# phase-90.net
KiCad netlist of a schematic drawn in EAGLE
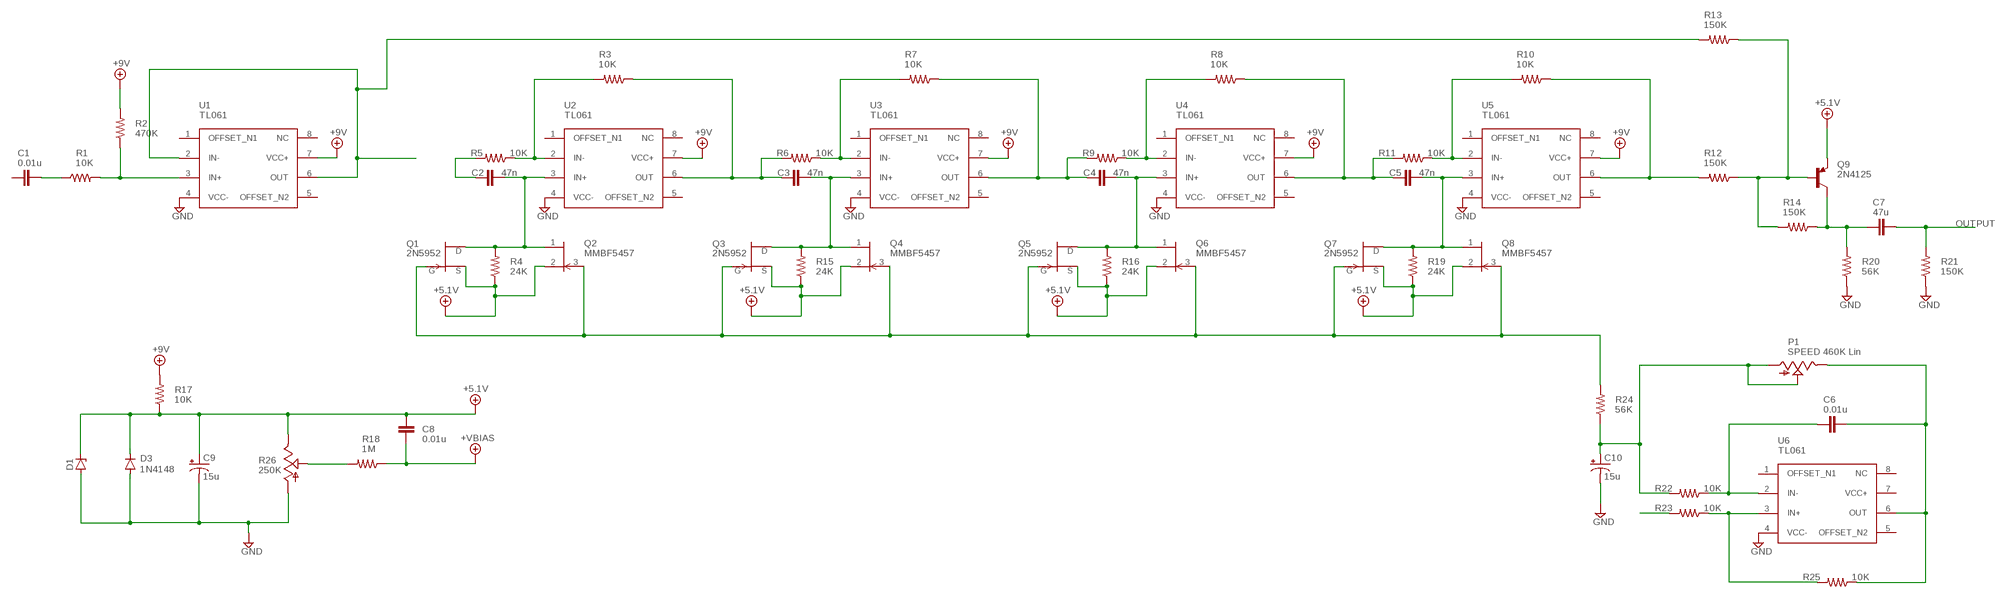
[diagram p0: schematic, sheet 1]

(export (version "E")
  (design (tool "Eeschema 10.0.6"))
  (components
    (comp (ref "C1")
      (value "0.01u")
      (footprint "eagle-import:C050-024X044")
      (libsource (lib "eagle-import") (part "C-EU050-024X044"))
    )
    (comp (ref "C2")
      (value "47n")
      (footprint "eagle-import:C050-024X044")
      (libsource (lib "eagle-import") (part "C-EU050-024X044"))
    )
    (comp (ref "C3")
      (value "47n")
      (footprint "eagle-import:C050-024X044")
      (libsource (lib "eagle-import") (part "C-EU050-024X044"))
    )
    (comp (ref "C4")
      (value "47n")
      (footprint "eagle-import:C050-024X044")
      (libsource (lib "eagle-import") (part "C-EU050-024X044"))
    )
    (comp (ref "C5")
      (value "47n")
      (footprint "eagle-import:C050-024X044")
      (libsource (lib "eagle-import") (part "C-EU050-024X044"))
    )
    (comp (ref "C6")
      (value "0.01u")
      (footprint "eagle-import:C050-024X044")
      (libsource (lib "eagle-import") (part "C-EU050-024X044"))
    )
    (comp (ref "C7")
      (value "47u")
      (footprint "eagle-import:C050-024X044")
      (libsource (lib "eagle-import") (part "C-EU050-024X044"))
    )
    (comp (ref "C8")
      (value "0.01u")
      (footprint "eagle-import:C050-024X044")
      (libsource (lib "eagle-import") (part "C-EU050-024X044"))
    )
    (comp (ref "C9")
      (value "15u")
      (footprint "eagle-import:E3,5-8")
      (libsource (lib "eagle-import") (part "CPOL-USE3.5-8"))
    )
    (comp (ref "C10")
      (value "15u")
      (footprint "eagle-import:E3,5-8")
      (libsource (lib "eagle-import") (part "CPOL-USE3.5-8"))
    )
    (comp (ref "D1")
      (value "ZENER-DIODEDO34-7")
      (footprint "eagle-import:DO34Z7")
      (libsource (lib "eagle-import") (part "ZENER-DIODEDO34-7"))
    )
    (comp (ref "D3")
      (value "1N4148")
      (footprint "eagle-import:DO35-7")
      (libsource (lib "eagle-import") (part "1N4148DO35-7"))
    )
    (comp (ref "P1")
      (value "SPEED 460K Lin")
      (footprint "eagle-import:POT-5.08MM")
      (libsource (lib "eagle-import") (part "POT"))
    )
    (comp (ref "Q1")
      (value "2N5952")
      (footprint "eagle-import:TO-92")
      (libsource (lib "eagle-import") (part "2N5950"))
    )
    (comp (ref "Q2")
      (value "MMBF5457")
      (footprint "eagle-import:SOT23")
      (libsource (lib "eagle-import") (part "MMBF5457"))
    )
    (comp (ref "Q3")
      (value "2N5952")
      (footprint "eagle-import:TO-92")
      (libsource (lib "eagle-import") (part "2N5950"))
    )
    (comp (ref "Q4")
      (value "MMBF5457")
      (footprint "eagle-import:SOT23")
      (libsource (lib "eagle-import") (part "MMBF5457"))
    )
    (comp (ref "Q5")
      (value "2N5952")
      (footprint "eagle-import:TO-92")
      (libsource (lib "eagle-import") (part "2N5950"))
    )
    (comp (ref "Q6")
      (value "MMBF5457")
      (footprint "eagle-import:SOT23")
      (libsource (lib "eagle-import") (part "MMBF5457"))
    )
    (comp (ref "Q7")
      (value "2N5952")
      (footprint "eagle-import:TO-92")
      (libsource (lib "eagle-import") (part "2N5950"))
    )
    (comp (ref "Q8")
      (value "MMBF5457")
      (footprint "eagle-import:SOT23")
      (libsource (lib "eagle-import") (part "MMBF5457"))
    )
    (comp (ref "Q9")
      (value "2N4125")
      (footprint "eagle-import:TO92")
      (libsource (lib "eagle-import") (part "-PNP-TO92"))
    )
    (comp (ref "R1")
      (value "10K")
      (footprint "eagle-import:0309_12")
      (libsource (lib "eagle-import") (part "R-US_0309/12"))
    )
    (comp (ref "R2")
      (value "470K")
      (footprint "eagle-import:0309_12")
      (libsource (lib "eagle-import") (part "R-US_0309/12"))
    )
    (comp (ref "R3")
      (value "10K")
      (footprint "eagle-import:0309_12")
      (libsource (lib "eagle-import") (part "R-US_0309/12"))
    )
    (comp (ref "R4")
      (value "24K")
      (footprint "eagle-import:0309_12")
      (libsource (lib "eagle-import") (part "R-US_0309/12"))
    )
    (comp (ref "R5")
      (value "10K")
      (footprint "eagle-import:0309_12")
      (libsource (lib "eagle-import") (part "R-US_0309/12"))
    )
    (comp (ref "R6")
      (value "10K")
      (footprint "eagle-import:0309_12")
      (libsource (lib "eagle-import") (part "R-US_0309/12"))
    )
    (comp (ref "R7")
      (value "10K")
      (footprint "eagle-import:0309_12")
      (libsource (lib "eagle-import") (part "R-US_0309/12"))
    )
    (comp (ref "R8")
      (value "10K")
      (footprint "eagle-import:0309_12")
      (libsource (lib "eagle-import") (part "R-US_0309/12"))
    )
    (comp (ref "R9")
      (value "10K")
      (footprint "eagle-import:0309_12")
      (libsource (lib "eagle-import") (part "R-US_0309/12"))
    )
    (comp (ref "R10")
      (value "10K")
      (footprint "eagle-import:0309_12")
      (libsource (lib "eagle-import") (part "R-US_0309/12"))
    )
    (comp (ref "R11")
      (value "10K")
      (footprint "eagle-import:0309_12")
      (libsource (lib "eagle-import") (part "R-US_0309/12"))
    )
    (comp (ref "R12")
      (value "150K")
      (footprint "eagle-import:0309_12")
      (libsource (lib "eagle-import") (part "R-US_0309/12"))
    )
    (comp (ref "R13")
      (value "150K")
      (footprint "eagle-import:0309_12")
      (libsource (lib "eagle-import") (part "R-US_0309/12"))
    )
    (comp (ref "R14")
      (value "150K")
      (footprint "eagle-import:0309_12")
      (libsource (lib "eagle-import") (part "R-US_0309/12"))
    )
    (comp (ref "R15")
      (value "24K")
      (footprint "eagle-import:0309_12")
      (libsource (lib "eagle-import") (part "R-US_0309/12"))
    )
    (comp (ref "R16")
      (value "24K")
      (footprint "eagle-import:0309_12")
      (libsource (lib "eagle-import") (part "R-US_0309/12"))
    )
    (comp (ref "R17")
      (value "10K")
      (footprint "eagle-import:0309_12")
      (libsource (lib "eagle-import") (part "R-US_0309/12"))
    )
    (comp (ref "R18")
      (value "1M")
      (footprint "eagle-import:0309_12")
      (libsource (lib "eagle-import") (part "R-US_0309/12"))
    )
    (comp (ref "R19")
      (value "24K")
      (footprint "eagle-import:0309_12")
      (libsource (lib "eagle-import") (part "R-US_0309/12"))
    )
    (comp (ref "R20")
      (value "56K")
      (footprint "eagle-import:0309_12")
      (libsource (lib "eagle-import") (part "R-US_0309/12"))
    )
    (comp (ref "R21")
      (value "150K")
      (footprint "eagle-import:0309_12")
      (libsource (lib "eagle-import") (part "R-US_0309/12"))
    )
    (comp (ref "R22")
      (value "10K")
      (footprint "eagle-import:0309_12")
      (libsource (lib "eagle-import") (part "R-US_0309/12"))
    )
    (comp (ref "R23")
      (value "10K")
      (footprint "eagle-import:0309_12")
      (libsource (lib "eagle-import") (part "R-US_0309/12"))
    )
    (comp (ref "R24")
      (value "56K")
      (footprint "eagle-import:0309_12")
      (libsource (lib "eagle-import") (part "R-US_0309/12"))
    )
    (comp (ref "R25")
      (value "10K")
      (footprint "eagle-import:0309_12")
      (libsource (lib "eagle-import") (part "R-US_0309/12"))
    )
    (comp (ref "R26")
      (value "250K")
      (footprint "eagle-import:CA6V")
      (libsource (lib "eagle-import") (part "TRIM_US-CA6V"))
    )
    (comp (ref "U1")
      (value "TL061")
      (footprint "eagle-import:DIL08")
      (libsource (lib "eagle-import") (part "TL061"))
    )
    (comp (ref "U2")
      (value "TL061")
      (footprint "eagle-import:DIL08")
      (libsource (lib "eagle-import") (part "TL061"))
    )
    (comp (ref "U3")
      (value "TL061")
      (footprint "eagle-import:DIL08")
      (libsource (lib "eagle-import") (part "TL061"))
    )
    (comp (ref "U4")
      (value "TL061")
      (footprint "eagle-import:DIL08")
      (libsource (lib "eagle-import") (part "TL061"))
    )
    (comp (ref "U5")
      (value "TL061")
      (footprint "eagle-import:DIL08")
      (libsource (lib "eagle-import") (part "TL061"))
    )
    (comp (ref "U6")
      (value "TL061")
      (footprint "eagle-import:DIL08")
      (libsource (lib "eagle-import") (part "TL061"))
    )
  )
  (nets
    (net (code "1") (name "+5.1V") (class "Default")
      (node (ref "C8") (pin "2") (pinfunction "2_2") (pintype "passive"))
      (node (ref "C9") (pin "+") (pinfunction "+_+") (pintype "passive"))
      (node (ref "D1") (pin "C") (pinfunction "C_C") (pintype "passive"))
      (node (ref "D3") (pin "C") (pinfunction "C_C") (pintype "passive"))
      (node (ref "Q1") (pin "2") (pinfunction "S_2") (pintype "passive"))
      (node (ref "Q2") (pin "2") (pinfunction "S_2") (pintype "passive"))
      (node (ref "Q3") (pin "2") (pinfunction "S_2") (pintype "passive"))
      (node (ref "Q4") (pin "2") (pinfunction "S_2") (pintype "passive"))
      (node (ref "Q5") (pin "2") (pinfunction "S_2") (pintype "passive"))
      (node (ref "Q6") (pin "2") (pinfunction "S_2") (pintype "passive"))
      (node (ref "Q7") (pin "2") (pinfunction "S_2") (pintype "passive"))
      (node (ref "Q8") (pin "2") (pinfunction "S_2") (pintype "passive"))
      (node (ref "Q9") (pin "1") (pinfunction "E_1") (pintype "passive"))
      (node (ref "R15") (pin "1") (pinfunction "1_1") (pintype "passive"))
      (node (ref "R16") (pin "1") (pinfunction "1_1") (pintype "passive"))
      (node (ref "R17") (pin "1") (pinfunction "1_1") (pintype "passive"))
      (node (ref "R19") (pin "1") (pinfunction "1_1") (pintype "passive"))
      (node (ref "R26") (pin "E") (pinfunction "E_E") (pintype "passive"))
      (node (ref "R4") (pin "1") (pinfunction "1_1") (pintype "passive"))
    )
    (net (code "2") (name "+9V") (class "Default")
      (node (ref "R17") (pin "2") (pinfunction "2_2") (pintype "passive"))
      (node (ref "R2") (pin "2") (pinfunction "2_2") (pintype "passive"))
      (node (ref "U1") (pin "7") (pinfunction "VCC+_7") (pintype "bidirectional"))
      (node (ref "U2") (pin "7") (pinfunction "VCC+_7") (pintype "bidirectional"))
      (node (ref "U3") (pin "7") (pinfunction "VCC+_7") (pintype "bidirectional"))
      (node (ref "U4") (pin "7") (pinfunction "VCC+_7") (pintype "bidirectional"))
      (node (ref "U5") (pin "7") (pinfunction "VCC+_7") (pintype "bidirectional"))
    )
    (net (code "3") (name "+VBIAS") (class "Default")
      (node (ref "C8") (pin "1") (pinfunction "1_1") (pintype "passive"))
      (node (ref "R18") (pin "1") (pinfunction "1_1") (pintype "passive"))
    )
    (net (code "4") (name "/OUTPUT") (class "Default")
      (node (ref "C7") (pin "2") (pinfunction "2_2") (pintype "passive"))
      (node (ref "R21") (pin "2") (pinfunction "2_2") (pintype "passive"))
    )
    (net (code "5") (name "GND") (class "Default")
      (node (ref "C10") (pin "-") (pinfunction "-_-") (pintype "passive"))
      (node (ref "C9") (pin "-") (pinfunction "-_-") (pintype "passive"))
      (node (ref "D1") (pin "A") (pinfunction "A_A") (pintype "passive"))
      (node (ref "D3") (pin "A") (pinfunction "A_A") (pintype "passive"))
      (node (ref "R20") (pin "1") (pinfunction "1_1") (pintype "passive"))
      (node (ref "R21") (pin "1") (pinfunction "1_1") (pintype "passive"))
      (node (ref "R26") (pin "A") (pinfunction "A_A") (pintype "passive"))
      (node (ref "U1") (pin "4") (pinfunction "VCC-_4") (pintype "bidirectional"))
      (node (ref "U2") (pin "4") (pinfunction "VCC-_4") (pintype "bidirectional"))
      (node (ref "U3") (pin "4") (pinfunction "VCC-_4") (pintype "bidirectional"))
      (node (ref "U4") (pin "4") (pinfunction "VCC-_4") (pintype "bidirectional"))
      (node (ref "U5") (pin "4") (pinfunction "VCC-_4") (pintype "bidirectional"))
      (node (ref "U6") (pin "4") (pinfunction "VCC-_4") (pintype "bidirectional"))
    )
    (net (code "6") (name "Net-(C1-Pad2)") (class "Default")
      (node (ref "C1") (pin "2") (pinfunction "2_2") (pintype "passive"))
      (node (ref "R1") (pin "1") (pinfunction "1_1") (pintype "passive"))
    )
    (net (code "7") (name "Net-(C2-Pad1)") (class "Default")
      (node (ref "C2") (pin "1") (pinfunction "1_1") (pintype "passive"))
      (node (ref "R5") (pin "2") (pinfunction "2_2") (pintype "passive"))
    )
    (net (code "8") (name "Net-(C10-Pad+)") (class "Default")
      (node (ref "C10") (pin "+") (pinfunction "+_+") (pintype "passive"))
      (node (ref "P1") (pin "1") (pinfunction "1_1") (pintype "passive"))
      (node (ref "P1") (pin "2") (pinfunction "2_2") (pintype "passive"))
      (node (ref "R22") (pin "2") (pinfunction "2_2") (pintype "passive"))
      (node (ref "R24") (pin "1") (pinfunction "1_1") (pintype "passive"))
    )
    (net (code "9") (name "Net-(Q1-D)") (class "Default")
      (node (ref "C2") (pin "2") (pinfunction "2_2") (pintype "passive"))
      (node (ref "Q1") (pin "3") (pinfunction "D_3") (pintype "passive"))
      (node (ref "Q2") (pin "1") (pinfunction "D_1") (pintype "passive"))
      (node (ref "R4") (pin "2") (pinfunction "2_2") (pintype "passive"))
      (node (ref "U2") (pin "3") (pinfunction "IN+_3") (pintype "bidirectional"))
    )
    (net (code "10") (name "Net-(Q1-G)") (class "Default")
      (node (ref "Q1") (pin "1") (pinfunction "G_1") (pintype "passive"))
      (node (ref "Q2") (pin "3") (pinfunction "G_3") (pintype "passive"))
      (node (ref "Q3") (pin "1") (pinfunction "G_1") (pintype "passive"))
      (node (ref "Q4") (pin "3") (pinfunction "G_3") (pintype "passive"))
      (node (ref "Q5") (pin "1") (pinfunction "G_1") (pintype "passive"))
      (node (ref "Q6") (pin "3") (pinfunction "G_3") (pintype "passive"))
      (node (ref "Q7") (pin "1") (pinfunction "G_1") (pintype "passive"))
      (node (ref "Q8") (pin "3") (pinfunction "G_3") (pintype "passive"))
      (node (ref "R24") (pin "2") (pinfunction "2_2") (pintype "passive"))
    )
    (net (code "11") (name "Net-(Q3-D)") (class "Default")
      (node (ref "C3") (pin "2") (pinfunction "2_2") (pintype "passive"))
      (node (ref "Q3") (pin "3") (pinfunction "D_3") (pintype "passive"))
      (node (ref "Q4") (pin "1") (pinfunction "D_1") (pintype "passive"))
      (node (ref "R15") (pin "2") (pinfunction "2_2") (pintype "passive"))
      (node (ref "U3") (pin "3") (pinfunction "IN+_3") (pintype "bidirectional"))
    )
    (net (code "12") (name "Net-(Q5-D)") (class "Default")
      (node (ref "C4") (pin "2") (pinfunction "2_2") (pintype "passive"))
      (node (ref "Q5") (pin "3") (pinfunction "D_3") (pintype "passive"))
      (node (ref "Q6") (pin "1") (pinfunction "D_1") (pintype "passive"))
      (node (ref "R16") (pin "2") (pinfunction "2_2") (pintype "passive"))
      (node (ref "U4") (pin "3") (pinfunction "IN+_3") (pintype "bidirectional"))
    )
    (net (code "13") (name "Net-(Q7-D)") (class "Default")
      (node (ref "C5") (pin "2") (pinfunction "2_2") (pintype "passive"))
      (node (ref "Q7") (pin "3") (pinfunction "D_3") (pintype "passive"))
      (node (ref "Q8") (pin "1") (pinfunction "D_1") (pintype "passive"))
      (node (ref "R19") (pin "2") (pinfunction "2_2") (pintype "passive"))
      (node (ref "U5") (pin "3") (pinfunction "IN+_3") (pintype "bidirectional"))
    )
    (net (code "14") (name "Net-(Q9-B)") (class "Default")
      (node (ref "Q9") (pin "2") (pinfunction "B_2") (pintype "passive"))
      (node (ref "R12") (pin "1") (pinfunction "1_1") (pintype "passive"))
      (node (ref "R13") (pin "1") (pinfunction "1_1") (pintype "passive"))
      (node (ref "R14") (pin "2") (pinfunction "2_2") (pintype "passive"))
    )
    (net (code "15") (name "Net-(Q9-C)") (class "Default")
      (node (ref "C7") (pin "1") (pinfunction "1_1") (pintype "passive"))
      (node (ref "Q9") (pin "3") (pinfunction "C_3") (pintype "passive"))
      (node (ref "R14") (pin "1") (pinfunction "1_1") (pintype "passive"))
      (node (ref "R20") (pin "2") (pinfunction "2_2") (pintype "passive"))
    )
    (net (code "16") (name "Net-(R18-Pad2)") (class "Default")
      (node (ref "R18") (pin "2") (pinfunction "2_2") (pintype "passive"))
      (node (ref "R26") (pin "S") (pinfunction "S_S") (pintype "passive"))
    )
    (net (code "17") (name "Net-(U1-IN+)") (class "Default")
      (node (ref "R1") (pin "2") (pinfunction "2_2") (pintype "passive"))
      (node (ref "R2") (pin "1") (pinfunction "1_1") (pintype "passive"))
      (node (ref "U1") (pin "3") (pinfunction "IN+_3") (pintype "bidirectional"))
    )
    (net (code "18") (name "Net-(U1-IN-)") (class "Default")
      (node (ref "R13") (pin "2") (pinfunction "2_2") (pintype "passive"))
      (node (ref "U1") (pin "2") (pinfunction "IN-_2") (pintype "bidirectional"))
      (node (ref "U1") (pin "6") (pinfunction "OUT_6") (pintype "bidirectional"))
    )
    (net (code "19") (name "Net-(U2-IN-)") (class "Default")
      (node (ref "R3") (pin "2") (pinfunction "2_2") (pintype "passive"))
      (node (ref "R5") (pin "1") (pinfunction "1_1") (pintype "passive"))
      (node (ref "U2") (pin "2") (pinfunction "IN-_2") (pintype "bidirectional"))
    )
    (net (code "20") (name "Net-(U2-OUT)") (class "Default")
      (node (ref "C3") (pin "1") (pinfunction "1_1") (pintype "passive"))
      (node (ref "R3") (pin "1") (pinfunction "1_1") (pintype "passive"))
      (node (ref "R6") (pin "2") (pinfunction "2_2") (pintype "passive"))
      (node (ref "U2") (pin "6") (pinfunction "OUT_6") (pintype "bidirectional"))
    )
    (net (code "21") (name "Net-(U3-IN-)") (class "Default")
      (node (ref "R6") (pin "1") (pinfunction "1_1") (pintype "passive"))
      (node (ref "R7") (pin "2") (pinfunction "2_2") (pintype "passive"))
      (node (ref "U3") (pin "2") (pinfunction "IN-_2") (pintype "bidirectional"))
    )
    (net (code "22") (name "Net-(U3-OUT)") (class "Default")
      (node (ref "C4") (pin "1") (pinfunction "1_1") (pintype "passive"))
      (node (ref "R7") (pin "1") (pinfunction "1_1") (pintype "passive"))
      (node (ref "R9") (pin "2") (pinfunction "2_2") (pintype "passive"))
      (node (ref "U3") (pin "6") (pinfunction "OUT_6") (pintype "bidirectional"))
    )
    (net (code "23") (name "Net-(U4-IN-)") (class "Default")
      (node (ref "R8") (pin "2") (pinfunction "2_2") (pintype "passive"))
      (node (ref "R9") (pin "1") (pinfunction "1_1") (pintype "passive"))
      (node (ref "U4") (pin "2") (pinfunction "IN-_2") (pintype "bidirectional"))
    )
    (net (code "24") (name "Net-(U4-OUT)") (class "Default")
      (node (ref "C5") (pin "1") (pinfunction "1_1") (pintype "passive"))
      (node (ref "R11") (pin "2") (pinfunction "2_2") (pintype "passive"))
      (node (ref "R8") (pin "1") (pinfunction "1_1") (pintype "passive"))
      (node (ref "U4") (pin "6") (pinfunction "OUT_6") (pintype "bidirectional"))
    )
    (net (code "25") (name "Net-(U5-IN-)") (class "Default")
      (node (ref "R10") (pin "2") (pinfunction "2_2") (pintype "passive"))
      (node (ref "R11") (pin "1") (pinfunction "1_1") (pintype "passive"))
      (node (ref "U5") (pin "2") (pinfunction "IN-_2") (pintype "bidirectional"))
    )
    (net (code "26") (name "Net-(U5-OUT)") (class "Default")
      (node (ref "R10") (pin "1") (pinfunction "1_1") (pintype "passive"))
      (node (ref "R12") (pin "2") (pinfunction "2_2") (pintype "passive"))
      (node (ref "U5") (pin "6") (pinfunction "OUT_6") (pintype "bidirectional"))
    )
    (net (code "27") (name "Net-(U6-IN+)") (class "Default")
      (node (ref "R23") (pin "1") (pinfunction "1_1") (pintype "passive"))
      (node (ref "R25") (pin "2") (pinfunction "2_2") (pintype "passive"))
      (node (ref "U6") (pin "3") (pinfunction "IN+_3") (pintype "bidirectional"))
    )
    (net (code "28") (name "Net-(U6-IN-)") (class "Default")
      (node (ref "C6") (pin "1") (pinfunction "1_1") (pintype "passive"))
      (node (ref "R22") (pin "1") (pinfunction "1_1") (pintype "passive"))
      (node (ref "U6") (pin "2") (pinfunction "IN-_2") (pintype "bidirectional"))
    )
    (net (code "29") (name "Net-(U6-OUT)") (class "Default")
      (node (ref "C6") (pin "2") (pinfunction "2_2") (pintype "passive"))
      (node (ref "P1") (pin "3") (pinfunction "3_3") (pintype "passive"))
      (node (ref "R25") (pin "1") (pinfunction "1_1") (pintype "passive"))
      (node (ref "U6") (pin "6") (pinfunction "OUT_6") (pintype "bidirectional"))
    )
    (net (code "30") (name "unconnected-(C1-Pad1)") (class "Default")
      (node (ref "C1") (pin "1") (pinfunction "1_1") (pintype "passive"))
    )
    (net (code "31") (name "unconnected-(R23-Pad2)") (class "Default")
      (node (ref "R23") (pin "2") (pinfunction "2_2") (pintype "passive"))
    )
    (net (code "32") (name "unconnected-(U1-NC-Pad8)") (class "Default")
      (node (ref "U1") (pin "8") (pinfunction "NC_8") (pintype "bidirectional"))
    )
    (net (code "33") (name "unconnected-(U1-OFFSET_N1-Pad1)") (class "Default")
      (node (ref "U1") (pin "1") (pinfunction "OFFSET_N1_1") (pintype "bidirectional"))
    )
    (net (code "34") (name "unconnected-(U1-OFFSET_N2-Pad5)") (class "Default")
      (node (ref "U1") (pin "5") (pinfunction "OFFSET_N2_5") (pintype "bidirectional"))
    )
    (net (code "35") (name "unconnected-(U2-NC-Pad8)") (class "Default")
      (node (ref "U2") (pin "8") (pinfunction "NC_8") (pintype "bidirectional"))
    )
    (net (code "36") (name "unconnected-(U2-OFFSET_N1-Pad1)") (class "Default")
      (node (ref "U2") (pin "1") (pinfunction "OFFSET_N1_1") (pintype "bidirectional"))
    )
    (net (code "37") (name "unconnected-(U2-OFFSET_N2-Pad5)") (class "Default")
      (node (ref "U2") (pin "5") (pinfunction "OFFSET_N2_5") (pintype "bidirectional"))
    )
    (net (code "38") (name "unconnected-(U3-NC-Pad8)") (class "Default")
      (node (ref "U3") (pin "8") (pinfunction "NC_8") (pintype "bidirectional"))
    )
    (net (code "39") (name "unconnected-(U3-OFFSET_N1-Pad1)") (class "Default")
      (node (ref "U3") (pin "1") (pinfunction "OFFSET_N1_1") (pintype "bidirectional"))
    )
    (net (code "40") (name "unconnected-(U3-OFFSET_N2-Pad5)") (class "Default")
      (node (ref "U3") (pin "5") (pinfunction "OFFSET_N2_5") (pintype "bidirectional"))
    )
    (net (code "41") (name "unconnected-(U4-NC-Pad8)") (class "Default")
      (node (ref "U4") (pin "8") (pinfunction "NC_8") (pintype "bidirectional"))
    )
    (net (code "42") (name "unconnected-(U4-OFFSET_N1-Pad1)") (class "Default")
      (node (ref "U4") (pin "1") (pinfunction "OFFSET_N1_1") (pintype "bidirectional"))
    )
    (net (code "43") (name "unconnected-(U4-OFFSET_N2-Pad5)") (class "Default")
      (node (ref "U4") (pin "5") (pinfunction "OFFSET_N2_5") (pintype "bidirectional"))
    )
    (net (code "44") (name "unconnected-(U5-NC-Pad8)") (class "Default")
      (node (ref "U5") (pin "8") (pinfunction "NC_8") (pintype "bidirectional"))
    )
    (net (code "45") (name "unconnected-(U5-OFFSET_N1-Pad1)") (class "Default")
      (node (ref "U5") (pin "1") (pinfunction "OFFSET_N1_1") (pintype "bidirectional"))
    )
    (net (code "46") (name "unconnected-(U5-OFFSET_N2-Pad5)") (class "Default")
      (node (ref "U5") (pin "5") (pinfunction "OFFSET_N2_5") (pintype "bidirectional"))
    )
    (net (code "47") (name "unconnected-(U6-NC-Pad8)") (class "Default")
      (node (ref "U6") (pin "8") (pinfunction "NC_8") (pintype "bidirectional"))
    )
    (net (code "48") (name "unconnected-(U6-OFFSET_N1-Pad1)") (class "Default")
      (node (ref "U6") (pin "1") (pinfunction "OFFSET_N1_1") (pintype "bidirectional"))
    )
    (net (code "49") (name "unconnected-(U6-OFFSET_N2-Pad5)") (class "Default")
      (node (ref "U6") (pin "5") (pinfunction "OFFSET_N2_5") (pintype "bidirectional"))
    )
    (net (code "50") (name "unconnected-(U6-VCC+-Pad7)") (class "Default")
      (node (ref "U6") (pin "7") (pinfunction "VCC+_7") (pintype "bidirectional"))
    )
  )
)
